# Sheet2.net
KiCad netlist of a schematic drawn in Altium Designer
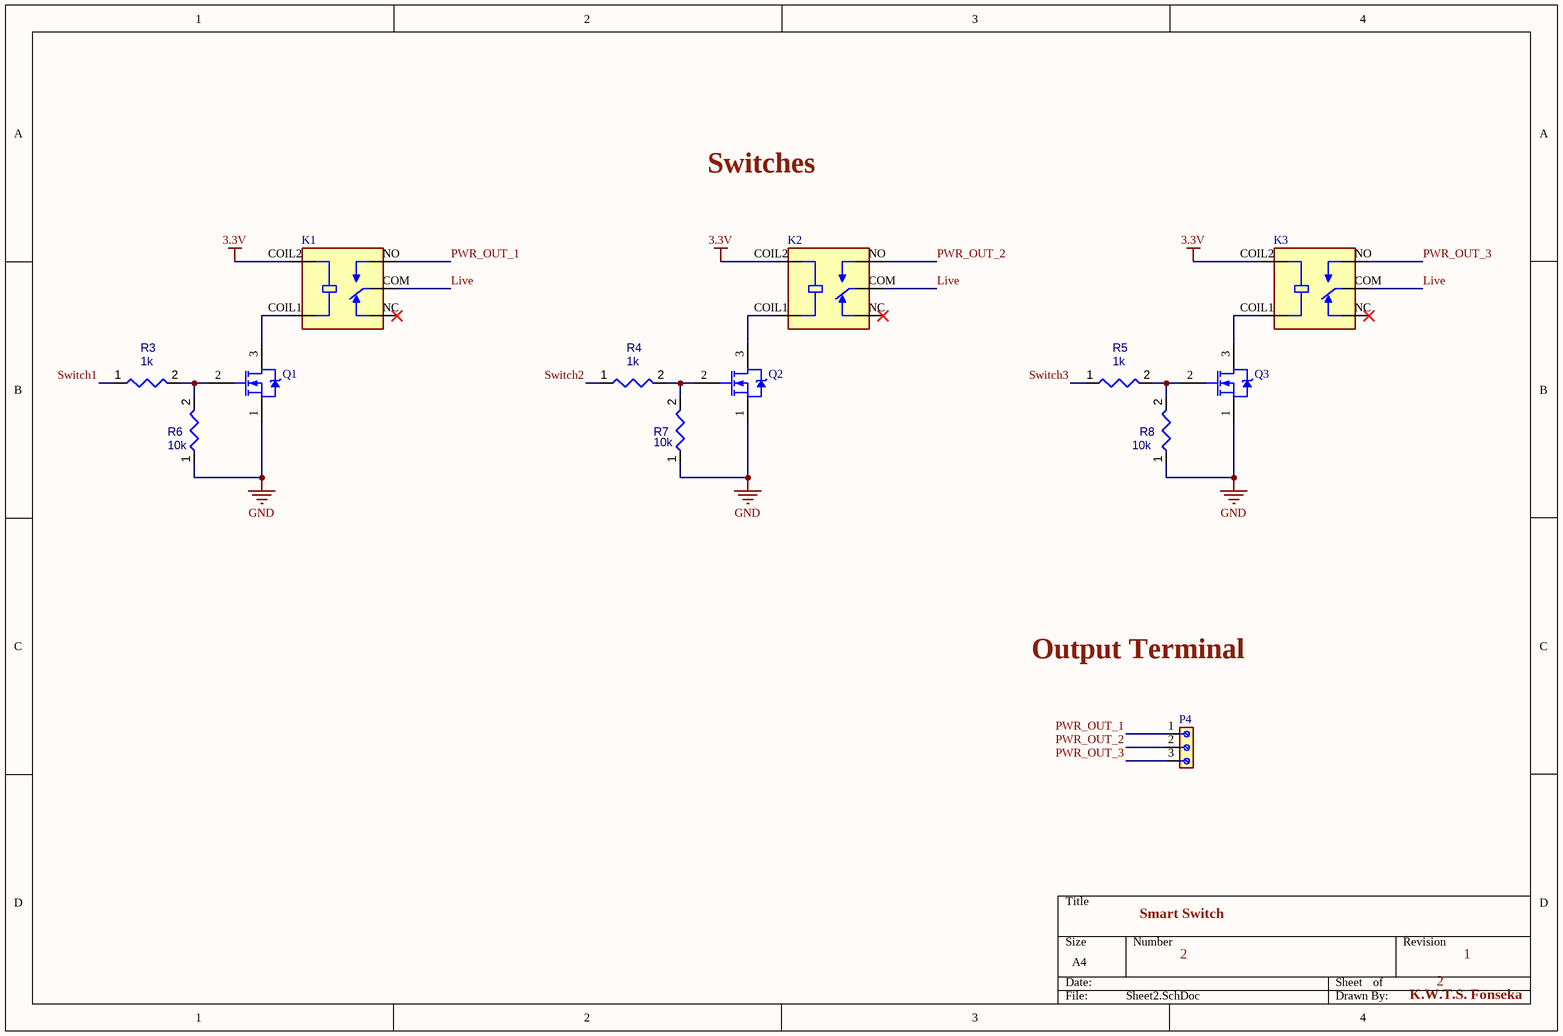
[diagram p0: Sheet2.SchDoc]

(export (version "E")
  (design (tool "Eeschema 10.0.6"))
  (components
    (comp (ref "K1")
      (value "SRD-03VDC-SL-C")
      (footprint "RELAY_SRD-03VDC-SL-C")
      (description "Relays General Purpose Non Latching 3VDC SPDT 10A (250VAC) Max 5PIN")
      (fields (field (name "MF") "Songle Relay"))
      (libsource (lib "SRD-03VDC-SL-C") (part "SRD-03VDC-SL-C"))
    )
    (comp (ref "K2")
      (value "SRD-03VDC-SL-C")
      (footprint "RELAY_SRD-03VDC-SL-C")
      (description "Relays General Purpose Non Latching 3VDC SPDT 10A (250VAC) Max 5PIN")
      (fields (field (name "MF") "Songle Relay"))
      (libsource (lib "SRD-03VDC-SL-C") (part "SRD-03VDC-SL-C"))
    )
    (comp (ref "K3")
      (value "SRD-03VDC-SL-C")
      (footprint "RELAY_SRD-03VDC-SL-C")
      (description "Relays General Purpose Non Latching 3VDC SPDT 10A (250VAC) Max 5PIN")
      (fields (field (name "MF") "Songle Relay"))
      (libsource (lib "SRD-03VDC-SL-C") (part "SRD-03VDC-SL-C"))
    )
    (comp (ref "P4")
      (value "~")
      (footprint "691502710003")
      (description "5.00 MM TERMINAL BLOCK, HORIZONT")
      (fields (field (name "MF") "WÃ¼rth Elektronik") (field (name "MP") "691502710003"))
      (libsource (lib "Tharusha Fonseka- UoM") (part "691502710003"))
    )
    (comp (ref "Q1")
      (value "2N7000")
      (footprint "ONSC-TO-92-3-29-11")
      (description "Small Signal MOSFET, 200 mA, 60 V, N-Channel, 3-Pin TO-92, Bulk Box")
      (fields (field (name "MANUFACTURER") "On Semiconductor"))
      (libsource (lib "Altium Content Vault") (part "ONSC-NMOS-S1G2D3-3"))
    )
    (comp (ref "Q2")
      (value "2N7000")
      (footprint "ONSC-TO-92-3-29-11")
      (description "Small Signal MOSFET, 200 mA, 60 V, N-Channel, 3-Pin TO-92, Bulk Box")
      (fields (field (name "MANUFACTURER") "On Semiconductor"))
      (libsource (lib "Altium Content Vault") (part "ONSC-NMOS-S1G2D3-3"))
    )
    (comp (ref "Q3")
      (value "2N7000")
      (footprint "ONSC-TO-92-3-29-11")
      (description "Small Signal MOSFET, 200 mA, 60 V, N-Channel, 3-Pin TO-92, Bulk Box")
      (fields (field (name "MANUFACTURER") "On Semiconductor"))
      (libsource (lib "Altium Content Vault") (part "ONSC-NMOS-S1G2D3-3"))
    )
    (comp (ref "R3")
      (value "1k")
      (footprint "RESC2013X50X35ML15T15")
      (description "Chip Resistor, 10 KOhm, +/- 1%, 125 mW, -55 to 155 degC, 0805 (2012 Metric)")
      (fields (field (name "TOLERANCE") "1%") (field (name "POWER") "125mW"))
      (libsource (lib "Tharusha Fonseka- UoM") (part "RES-2"))
    )
    (comp (ref "R4")
      (value "1k")
      (footprint "RESC2013X50X35ML15T15")
      (description "Chip Resistor, 10 KOhm, +/- 1%, 125 mW, -55 to 155 degC, 0805 (2012 Metric)")
      (fields (field (name "TOLERANCE") "1%") (field (name "POWER") "125mW"))
      (libsource (lib "Tharusha Fonseka- UoM") (part "RES-2"))
    )
    (comp (ref "R5")
      (value "1k")
      (footprint "RESC2013X50X35ML15T15")
      (description "Chip Resistor, 10 KOhm, +/- 1%, 125 mW, -55 to 155 degC, 0805 (2012 Metric)")
      (fields (field (name "TOLERANCE") "1%") (field (name "POWER") "125mW"))
      (libsource (lib "Tharusha Fonseka- UoM") (part "RES-2"))
    )
    (comp (ref "R6")
      (value "10k")
      (footprint "RESC2013X70X40ML20T20")
      (description "Chip Resistor, 100 KOhm, +/- 1%, 0.125 W, -55 to 155 degC, 0805 (2012 Metric)")
      (fields (field (name "TOLERANCE") "1%") (field (name "POWER") "125mW"))
      (libsource (lib "Tharusha Fonseka- UoM") (part "RES-2"))
    )
    (comp (ref "R7")
      (value "10k")
      (footprint "RESC2013X70X40ML20T20")
      (description "Chip Resistor, 100 KOhm, +/- 1%, 0.125 W, -55 to 155 degC, 0805 (2012 Metric)")
      (fields (field (name "TOLERANCE") "1%") (field (name "POWER") "125mW"))
      (libsource (lib "Tharusha Fonseka- UoM") (part "RES-2"))
    )
    (comp (ref "R8")
      (value "10k")
      (footprint "RESC2013X70X40ML20T20")
      (description "Chip Resistor, 100 KOhm, +/- 1%, 0.125 W, -55 to 155 degC, 0805 (2012 Metric)")
      (fields (field (name "TOLERANCE") "1%") (field (name "POWER") "125mW"))
      (libsource (lib "Tharusha Fonseka- UoM") (part "RES-2"))
    )
  )
  (nets
    (net (code "1") (name "/Live") (class "Default")
      (node (ref "K1") (pin "COM") (pinfunction "COM_COM") (pintype "passive"))
      (node (ref "K2") (pin "COM") (pinfunction "COM_COM") (pintype "passive"))
      (node (ref "K3") (pin "COM") (pinfunction "COM_COM") (pintype "passive"))
    )
    (net (code "2") (name "/PWR_OUT_1") (class "Default")
      (node (ref "K1") (pin "NO") (pinfunction "NO_NO") (pintype "passive"))
      (node (ref "P4") (pin "1") (pinfunction "1_1") (pintype "passive"))
    )
    (net (code "3") (name "/PWR_OUT_2") (class "Default")
      (node (ref "K2") (pin "NO") (pinfunction "NO_NO") (pintype "passive"))
      (node (ref "P4") (pin "2") (pinfunction "2_2") (pintype "passive"))
    )
    (net (code "4") (name "/PWR_OUT_3") (class "Default")
      (node (ref "K3") (pin "NO") (pinfunction "NO_NO") (pintype "passive"))
      (node (ref "P4") (pin "3") (pinfunction "3_3") (pintype "passive"))
    )
    (net (code "5") (name "/Switch1") (class "Default")
      (node (ref "R3") (pin "1") (pinfunction "1_1") (pintype "passive"))
    )
    (net (code "6") (name "/Switch2") (class "Default")
      (node (ref "R4") (pin "1") (pinfunction "1_1") (pintype "passive"))
    )
    (net (code "7") (name "/Switch3") (class "Default")
      (node (ref "R5") (pin "1") (pinfunction "1_1") (pintype "passive"))
    )
    (net (code "8") (name "3.3V") (class "Default")
      (node (ref "K1") (pin "COIL2") (pinfunction "COIL2_COIL2") (pintype "passive"))
      (node (ref "K2") (pin "COIL2") (pinfunction "COIL2_COIL2") (pintype "passive"))
      (node (ref "K3") (pin "COIL2") (pinfunction "COIL2_COIL2") (pintype "passive"))
    )
    (net (code "9") (name "GND") (class "Default")
      (node (ref "Q1") (pin "1") (pinfunction "S_1") (pintype "passive"))
      (node (ref "Q2") (pin "1") (pinfunction "S_1") (pintype "passive"))
      (node (ref "Q3") (pin "1") (pinfunction "S_1") (pintype "passive"))
      (node (ref "R6") (pin "1") (pinfunction "1_1") (pintype "passive"))
      (node (ref "R7") (pin "1") (pinfunction "1_1") (pintype "passive"))
      (node (ref "R8") (pin "1") (pinfunction "1_1") (pintype "passive"))
    )
    (net (code "10") (name "Net-(Q1-D)") (class "Default")
      (node (ref "K1") (pin "COIL1") (pinfunction "COIL1_COIL1") (pintype "passive"))
      (node (ref "Q1") (pin "3") (pinfunction "D_3") (pintype "passive"))
    )
    (net (code "11") (name "Net-(Q1-G)") (class "Default")
      (node (ref "Q1") (pin "2") (pinfunction "G_2") (pintype "passive"))
      (node (ref "R3") (pin "2") (pinfunction "2_2") (pintype "passive"))
      (node (ref "R6") (pin "2") (pinfunction "2_2") (pintype "passive"))
    )
    (net (code "12") (name "Net-(Q2-D)") (class "Default")
      (node (ref "K2") (pin "COIL1") (pinfunction "COIL1_COIL1") (pintype "passive"))
      (node (ref "Q2") (pin "3") (pinfunction "D_3") (pintype "passive"))
    )
    (net (code "13") (name "Net-(Q2-G)") (class "Default")
      (node (ref "Q2") (pin "2") (pinfunction "G_2") (pintype "passive"))
      (node (ref "R4") (pin "2") (pinfunction "2_2") (pintype "passive"))
      (node (ref "R7") (pin "2") (pinfunction "2_2") (pintype "passive"))
    )
    (net (code "14") (name "Net-(Q3-D)") (class "Default")
      (node (ref "K3") (pin "COIL1") (pinfunction "COIL1_COIL1") (pintype "passive"))
      (node (ref "Q3") (pin "3") (pinfunction "D_3") (pintype "passive"))
    )
    (net (code "15") (name "Net-(Q3-G)") (class "Default")
      (node (ref "Q3") (pin "2") (pinfunction "G_2") (pintype "passive"))
      (node (ref "R5") (pin "2") (pinfunction "2_2") (pintype "passive"))
      (node (ref "R8") (pin "2") (pinfunction "2_2") (pintype "passive"))
    )
    (net (code "16") (name "unconnected-(K1-PadNC)") (class "Default")
      (node (ref "K1") (pin "NC") (pinfunction "NC_NC") (pintype "passive+no_connect"))
    )
    (net (code "17") (name "unconnected-(K2-PadNC)") (class "Default")
      (node (ref "K2") (pin "NC") (pinfunction "NC_NC") (pintype "passive+no_connect"))
    )
    (net (code "18") (name "unconnected-(K3-PadNC)") (class "Default")
      (node (ref "K3") (pin "NC") (pinfunction "NC_NC") (pintype "passive+no_connect"))
    )
  )
)
